# Rear_brake_lamp_v3.net
KiCad netlist of a schematic drawn in EAGLE
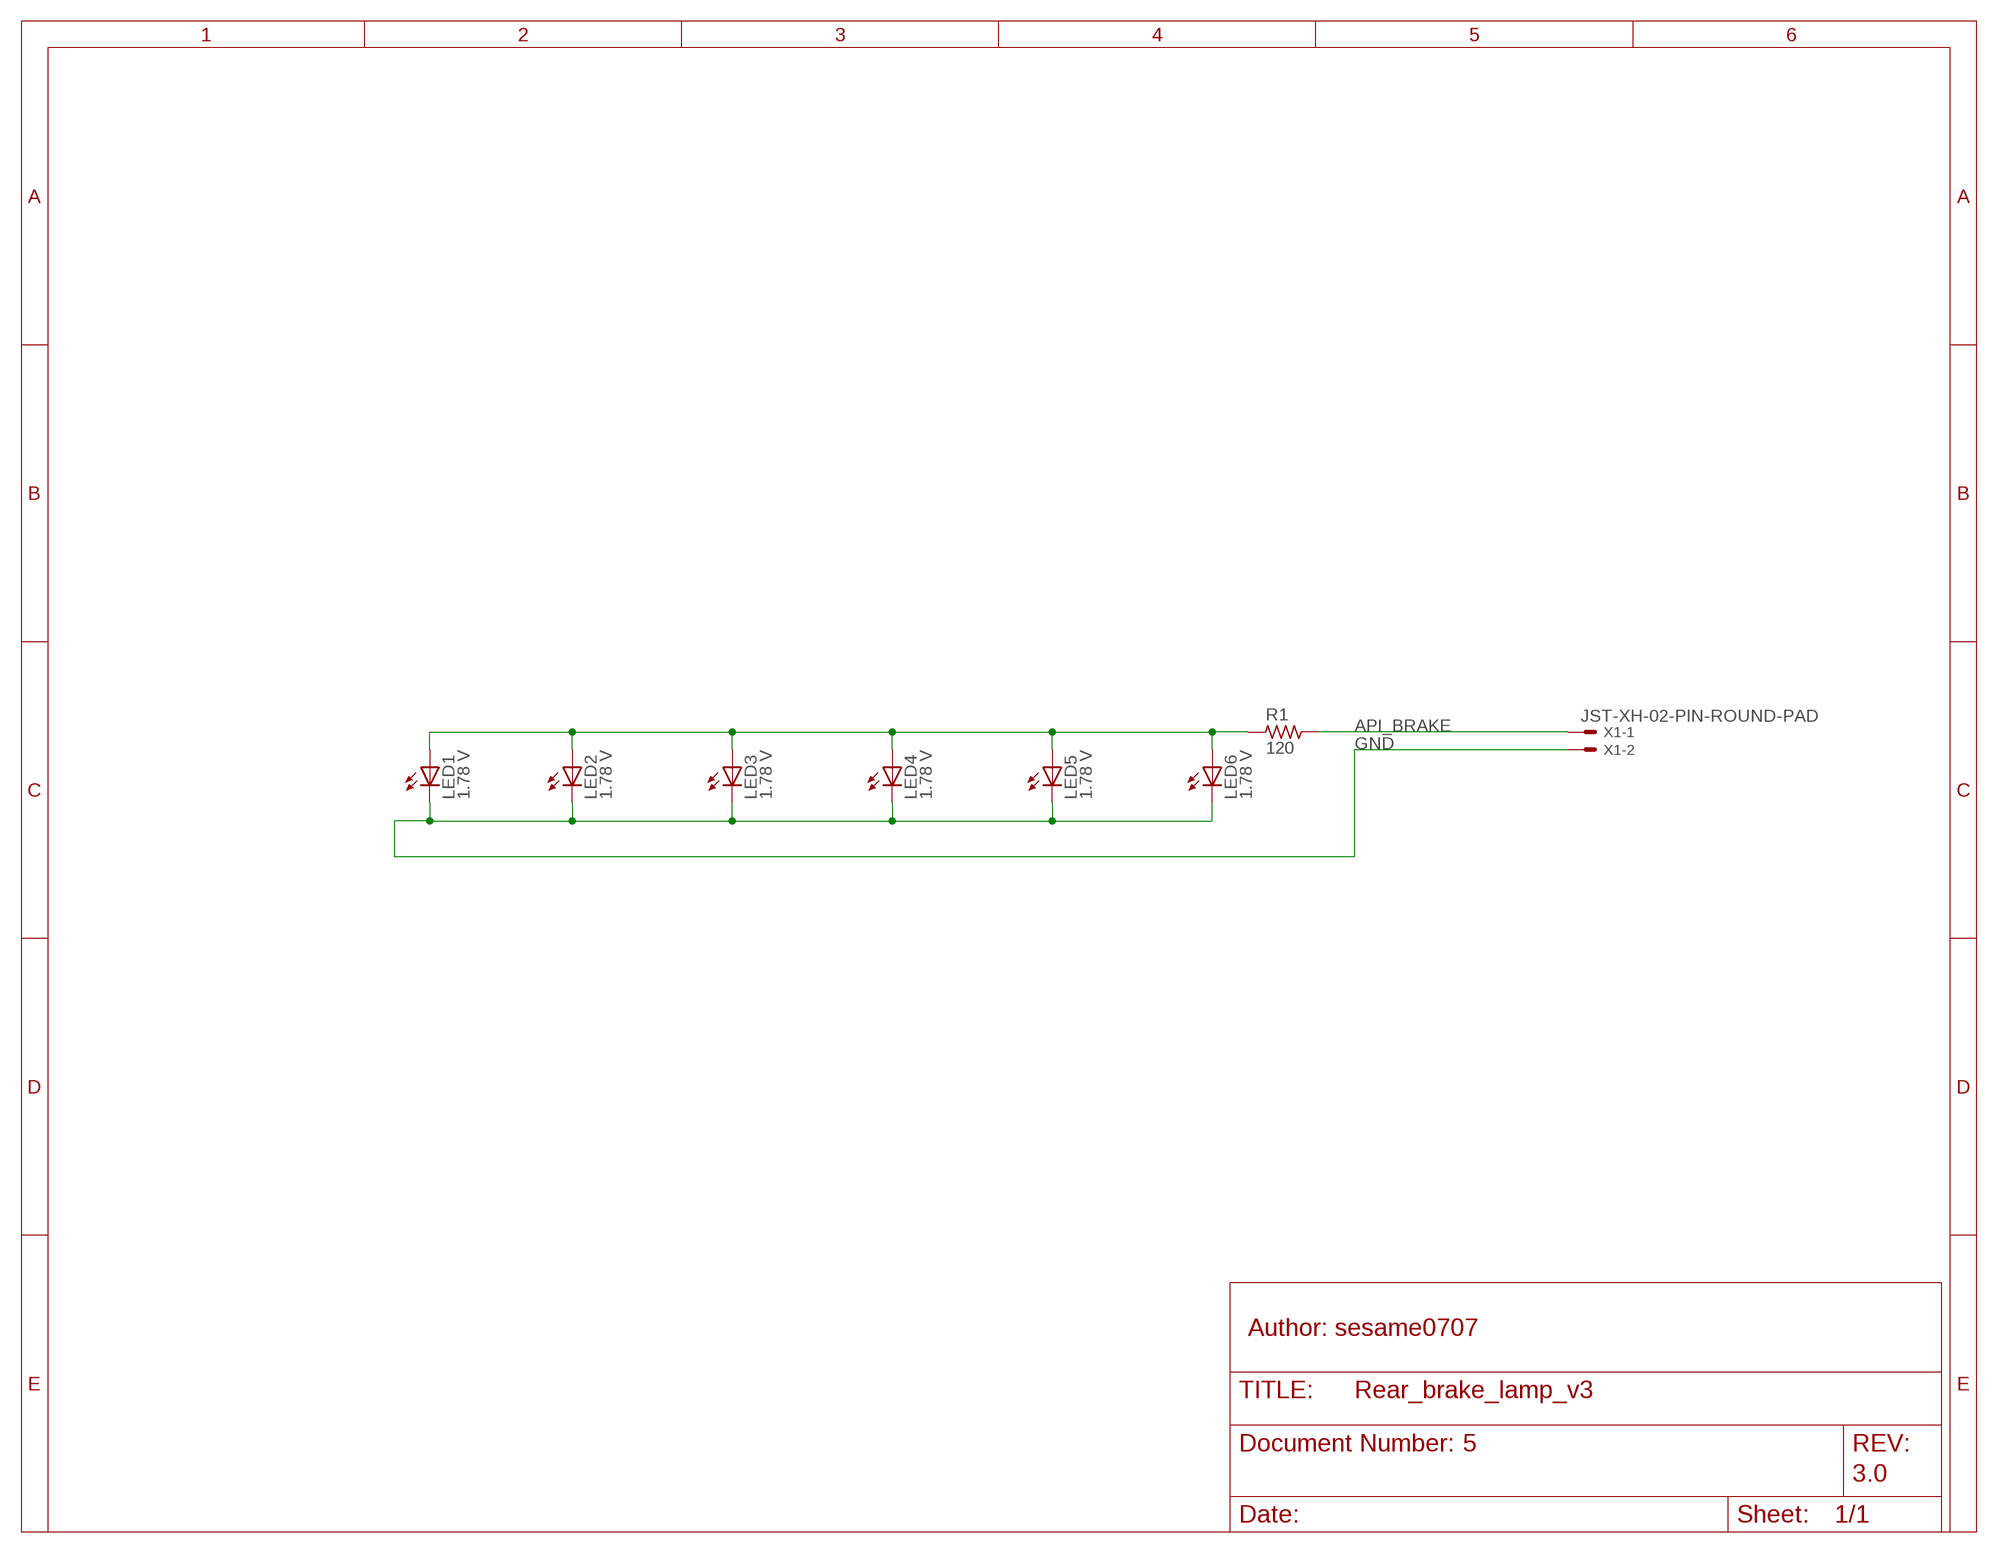
[diagram p0: schematic, sheet 1]

(export (version "E")
  (design (tool "Eeschema 10.0.6"))
  (components
    (comp (ref "LED1")
      (value "1.78 V")
      (footprint "eagle-import:LED5MM")
      (libsource (lib "eagle-import") (part "LED5MM"))
    )
    (comp (ref "LED2")
      (value "1.78 V")
      (footprint "eagle-import:LED5MM")
      (libsource (lib "eagle-import") (part "LED5MM"))
    )
    (comp (ref "LED3")
      (value "1.78 V")
      (footprint "eagle-import:LED5MM")
      (libsource (lib "eagle-import") (part "LED5MM"))
    )
    (comp (ref "LED4")
      (value "1.78 V")
      (footprint "eagle-import:LED5MM")
      (libsource (lib "eagle-import") (part "LED5MM"))
    )
    (comp (ref "LED5")
      (value "1.78 V")
      (footprint "eagle-import:LED5MM")
      (libsource (lib "eagle-import") (part "LED5MM"))
    )
    (comp (ref "LED6")
      (value "1.78 V")
      (footprint "eagle-import:LED5MM")
      (libsource (lib "eagle-import") (part "LED5MM"))
    )
    (comp (ref "R1")
      (value "120")
      (footprint "eagle-import:R1206")
      (libsource (lib "eagle-import") (part "R_1206"))
    )
    (comp (ref "X1")
      (value "JST-XH-02-PIN-ROUND-PAD")
      (footprint "eagle-import:JST-XH-02-PACKAGE-ROUND-PAD")
      (libsource (lib "eagle-import") (part "JST-XH-02-PIN-ROUND-PAD"))
    )
  )
  (nets
    (net (code "1") (name "/API_BRAKE") (class "Default")
      (node (ref "LED1") (pin "A") (pinfunction "A_A") (pintype "passive"))
      (node (ref "LED2") (pin "A") (pinfunction "A_A") (pintype "passive"))
      (node (ref "LED3") (pin "A") (pinfunction "A_A") (pintype "passive"))
      (node (ref "LED4") (pin "A") (pinfunction "A_A") (pintype "passive"))
      (node (ref "LED5") (pin "A") (pinfunction "A_A") (pintype "passive"))
      (node (ref "LED6") (pin "A") (pinfunction "A_A") (pintype "passive"))
      (node (ref "R1") (pin "1") (pinfunction "1_1") (pintype "passive"))
    )
    (net (code "2") (name "/GND") (class "Default")
      (node (ref "LED1") (pin "K") (pinfunction "C_K") (pintype "passive"))
      (node (ref "LED2") (pin "K") (pinfunction "C_K") (pintype "passive"))
      (node (ref "LED3") (pin "K") (pinfunction "C_K") (pintype "passive"))
      (node (ref "LED4") (pin "K") (pinfunction "C_K") (pintype "passive"))
      (node (ref "LED5") (pin "K") (pinfunction "C_K") (pintype "passive"))
      (node (ref "LED6") (pin "K") (pinfunction "C_K") (pintype "passive"))
      (node (ref "X1") (pin "2") (pinfunction "S_2") (pintype "passive"))
    )
    (net (code "3") (name "Net-(X1A-S)") (class "Default")
      (node (ref "R1") (pin "2") (pinfunction "2_2") (pintype "passive"))
      (node (ref "X1") (pin "1") (pinfunction "S_1") (pintype "passive"))
    )
  )
)
